# Sheet1.net
KiCad netlist of a schematic drawn in Altium Designer
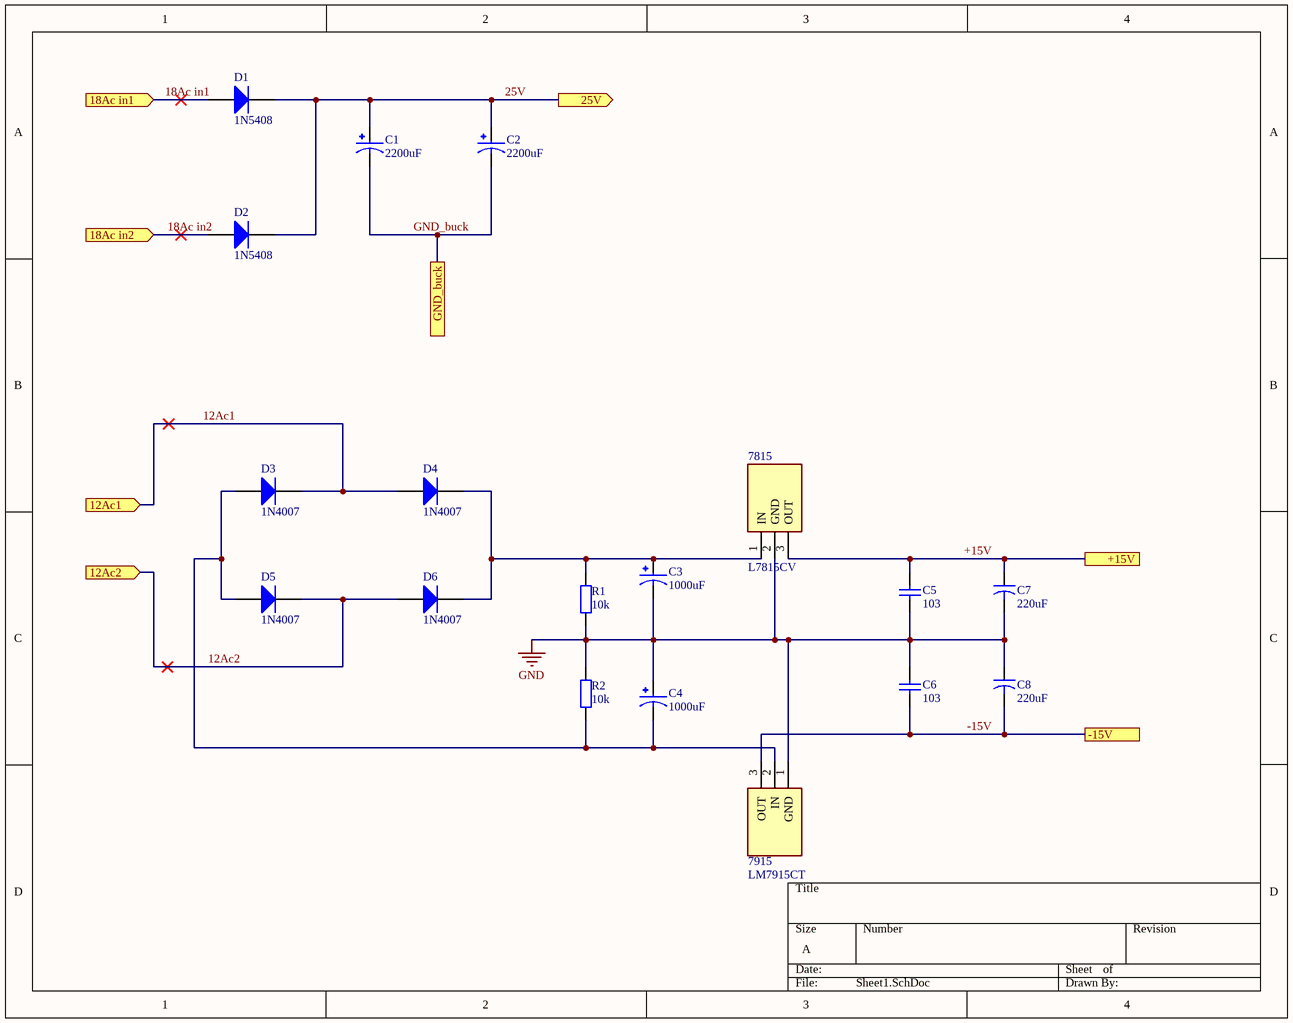
[diagram p0: Sheet1.SchDoc]

(export (version "E")
  (design (tool "Eeschema 10.0.6"))
  (components
    (comp (ref "7815")
      (value "L7815CV")
      (footprint "TO270P460X1020X2008-3P:TO270P460X1020X2008-3P")
      (description "L7815CV, Voltage Regulator, 1.5A 15 V, 3-Pin TO-220")
      (fields (field (name "MOUSER PART NUMBER") "511-L7815CV"))
      (libsource (lib "L7815CV") (part "L7815CV"))
    )
    (comp (ref "7915")
      (value "LM7915CT")
      (footprint "TO254P470X1016X2019-3P:TO254P470X1016X2019-3P")
      (description "ON Semiconductor LM7915CT Negative Voltage Regulator, 1A, -15 V, +/-4% 3-Pin, TO-220")
      (fields (field (name "MOUSER PART NUMBER") "512-LM7915CT"))
      (libsource (lib "LM7915CT") (part "LM7915CT"))
    )
    (comp (ref "C1")
      (value "2200uF")
      (footprint "CAPPRD500W60D1250H2500")
      (description "2200ÂµF 16V Aluminum Electrolytic Capacitors Radial, Can 7000 Hrs @ 105Â°C")
      (fields (field (name "MP") "EEUFM1C222") (field (name "MF") "Panasonic"))
      (libsource (lib "EEUFM1C222") (part "EEUFM1C222"))
    )
    (comp (ref "C2")
      (value "2200uF")
      (footprint "CAPPRD500W60D1250H2500")
      (description "2200ÂµF 16V Aluminum Electrolytic Capacitors Radial, Can 7000 Hrs @ 105Â°C")
      (fields (field (name "MP") "EEUFM1C222") (field (name "MF") "Panasonic"))
      (libsource (lib "EEUFM1C222") (part "EEUFM1C222"))
    )
    (comp (ref "C3")
      (value "1000uF")
      (footprint "CAPPRD500W60D1250H2500")
      (description "CAP ALUM 1000UF 20% 50V RADIAL")
      (fields (field (name "MF") "Panasonic") (field (name "MP") "EEU-HD1H102B"))
      (libsource (lib "EEUHD1H102B") (part "EEUHD1H102B"))
    )
    (comp (ref "C4")
      (value "1000uF")
      (footprint "CAPPRD500W60D1250H2500")
      (description "CAP ALUM 1000UF 20% 50V RADIAL")
      (fields (field (name "MF") "Panasonic") (field (name "MP") "EEU-HD1H102B"))
      (libsource (lib "EEUHD1H102B") (part "EEUHD1H102B"))
    )
    (comp (ref "C5")
      (value "103")
      (footprint "DE2E3SA103MA3BT02F:CAP_DE2E3SA103MA3BT02F")
      (description "Capacitor")
      (fields (field (name "PUBLISHER") "Altium Limited"))
      (libsource (lib "Miscellaneous Devices") (part "Cap"))
    )
    (comp (ref "C6")
      (value "103")
      (footprint "DE2E3SA103MA3BT02F:CAP_DE2E3SA103MA3BT02F")
      (description "Capacitor")
      (fields (field (name "PUBLISHER") "Altium Limited"))
      (libsource (lib "Miscellaneous Devices") (part "Cap"))
    )
    (comp (ref "C7")
      (value "220uF")
      (footprint "CAPR5-4X5")
      (description "Capacitor")
      (fields (field (name "PUBLISHER") "Altium Limited"))
      (libsource (lib "Miscellaneous Devices") (part "Cap2"))
    )
    (comp (ref "C8")
      (value "220uF")
      (footprint "CAPR5-4X5")
      (description "Capacitor")
      (fields (field (name "PUBLISHER") "Altium Limited"))
      (libsource (lib "Miscellaneous Devices") (part "Cap2"))
    )
    (comp (ref "D1")
      (value "1N5408")
      (footprint "DO-201AD")
      (description "3 Amp Medium Power Silicon Rectifier Diode")
      (fields (field (name "PUBLISHER") "Altium Limited"))
      (libsource (lib "Miscellaneous Devices") (part "Diode 1N5408"))
    )
    (comp (ref "D2")
      (value "1N5408")
      (footprint "DO-201AD")
      (description "3 Amp Medium Power Silicon Rectifier Diode")
      (fields (field (name "PUBLISHER") "Altium Limited"))
      (libsource (lib "Miscellaneous Devices") (part "Diode 1N5408"))
    )
    (comp (ref "D3")
      (value "1N4007")
      (footprint "DO-41")
      (description "1 Amp General Purpose Rectifier")
      (fields (field (name "PUBLISHER") "Altium Limited"))
      (libsource (lib "Miscellaneous Devices") (part "Diode 1N4007"))
    )
    (comp (ref "D4")
      (value "1N4007")
      (footprint "DO-41")
      (description "1 Amp General Purpose Rectifier")
      (fields (field (name "PUBLISHER") "Altium Limited"))
      (libsource (lib "Miscellaneous Devices") (part "Diode 1N4007"))
    )
    (comp (ref "D5")
      (value "1N4007")
      (footprint "DO-41")
      (description "1 Amp General Purpose Rectifier")
      (fields (field (name "PUBLISHER") "Altium Limited"))
      (libsource (lib "Miscellaneous Devices") (part "Diode 1N4007"))
    )
    (comp (ref "D6")
      (value "1N4007")
      (footprint "DO-41")
      (description "1 Amp General Purpose Rectifier")
      (fields (field (name "PUBLISHER") "Altium Limited"))
      (libsource (lib "Miscellaneous Devices") (part "Diode 1N4007"))
    )
    (comp (ref "R1")
      (value "10k")
      (footprint "AXIAL-0.4")
      (description "Resistor")
      (fields (field (name "PUBLISHER") "Altium Limited"))
      (libsource (lib "Miscellaneous Devices") (part "Res2"))
    )
    (comp (ref "R2")
      (value "10k")
      (footprint "AXIAL-0.4")
      (description "Resistor")
      (fields (field (name "PUBLISHER") "Altium Limited"))
      (libsource (lib "Miscellaneous Devices") (part "Res2"))
    )
  )
  (nets
    (net (code "1") (name "/+15V") (class "Default")
      (node (ref "7815") (pin "3") (pinfunction "OUT_3") (pintype "power_in"))
      (node (ref "C5") (pin "2") (pinfunction "2_2") (pintype "passive"))
      (node (ref "C7") (pin "1") (pinfunction "1_1") (pintype "passive"))
    )
    (net (code "2") (name "/-15V") (class "Default")
      (node (ref "7915") (pin "3") (pinfunction "OUT_3") (pintype "passive"))
      (node (ref "C6") (pin "1") (pinfunction "1_1") (pintype "passive"))
      (node (ref "C8") (pin "2") (pinfunction "2_2") (pintype "passive"))
    )
    (net (code "3") (name "/12Ac1") (class "Default")
      (node (ref "D3") (pin "2") (pinfunction "K_2") (pintype "passive"))
      (node (ref "D4") (pin "1") (pinfunction "A_1") (pintype "passive"))
    )
    (net (code "4") (name "/12Ac2") (class "Default")
      (node (ref "D5") (pin "2") (pinfunction "K_2") (pintype "passive"))
      (node (ref "D6") (pin "1") (pinfunction "A_1") (pintype "passive"))
    )
    (net (code "5") (name "/18Ac in1") (class "Default")
      (node (ref "D1") (pin "1") (pinfunction "A_1") (pintype "passive"))
    )
    (net (code "6") (name "/18Ac in2") (class "Default")
      (node (ref "D2") (pin "1") (pinfunction "A_1") (pintype "passive"))
    )
    (net (code "7") (name "/25V") (class "Default")
      (node (ref "C1") (pin "P") (pinfunction "P_P") (pintype "passive"))
      (node (ref "C2") (pin "P") (pinfunction "P_P") (pintype "passive"))
      (node (ref "D1") (pin "2") (pinfunction "K_2") (pintype "passive"))
      (node (ref "D2") (pin "2") (pinfunction "K_2") (pintype "passive"))
    )
    (net (code "8") (name "/GND_buck") (class "Default")
      (node (ref "C1") (pin "N") (pinfunction "N_N") (pintype "passive"))
      (node (ref "C2") (pin "N") (pinfunction "N_N") (pintype "passive"))
    )
    (net (code "9") (name "GND") (class "Default")
      (node (ref "7815") (pin "2") (pinfunction "GND_2") (pintype "power_in"))
      (node (ref "7915") (pin "1") (pinfunction "GND_1") (pintype "passive"))
      (node (ref "C3") (pin "N") (pinfunction "N_N") (pintype "passive"))
      (node (ref "C4") (pin "P") (pinfunction "P_P") (pintype "passive"))
      (node (ref "C5") (pin "1") (pinfunction "1_1") (pintype "passive"))
      (node (ref "C6") (pin "2") (pinfunction "2_2") (pintype "passive"))
      (node (ref "C7") (pin "2") (pinfunction "2_2") (pintype "passive"))
      (node (ref "C8") (pin "1") (pinfunction "1_1") (pintype "passive"))
      (node (ref "R1") (pin "1") (pinfunction "1_1") (pintype "passive"))
      (node (ref "R2") (pin "2") (pinfunction "2_2") (pintype "passive"))
    )
    (net (code "10") (name "Net-(7815-IN)") (class "Default")
      (node (ref "7815") (pin "1") (pinfunction "IN_1") (pintype "power_in"))
      (node (ref "C3") (pin "P") (pinfunction "P_P") (pintype "passive"))
      (node (ref "D4") (pin "2") (pinfunction "K_2") (pintype "passive"))
      (node (ref "D6") (pin "2") (pinfunction "K_2") (pintype "passive"))
      (node (ref "R1") (pin "2") (pinfunction "2_2") (pintype "passive"))
    )
    (net (code "11") (name "Net-(7915-IN)") (class "Default")
      (node (ref "7915") (pin "2") (pinfunction "IN_2") (pintype "passive"))
      (node (ref "C4") (pin "N") (pinfunction "N_N") (pintype "passive"))
      (node (ref "D3") (pin "1") (pinfunction "A_1") (pintype "passive"))
      (node (ref "D5") (pin "1") (pinfunction "A_1") (pintype "passive"))
      (node (ref "R2") (pin "1") (pinfunction "1_1") (pintype "passive"))
    )
  )
)
